# PS2_to_UART_revB.net
KiCad netlist of a schematic drawn in EAGLE
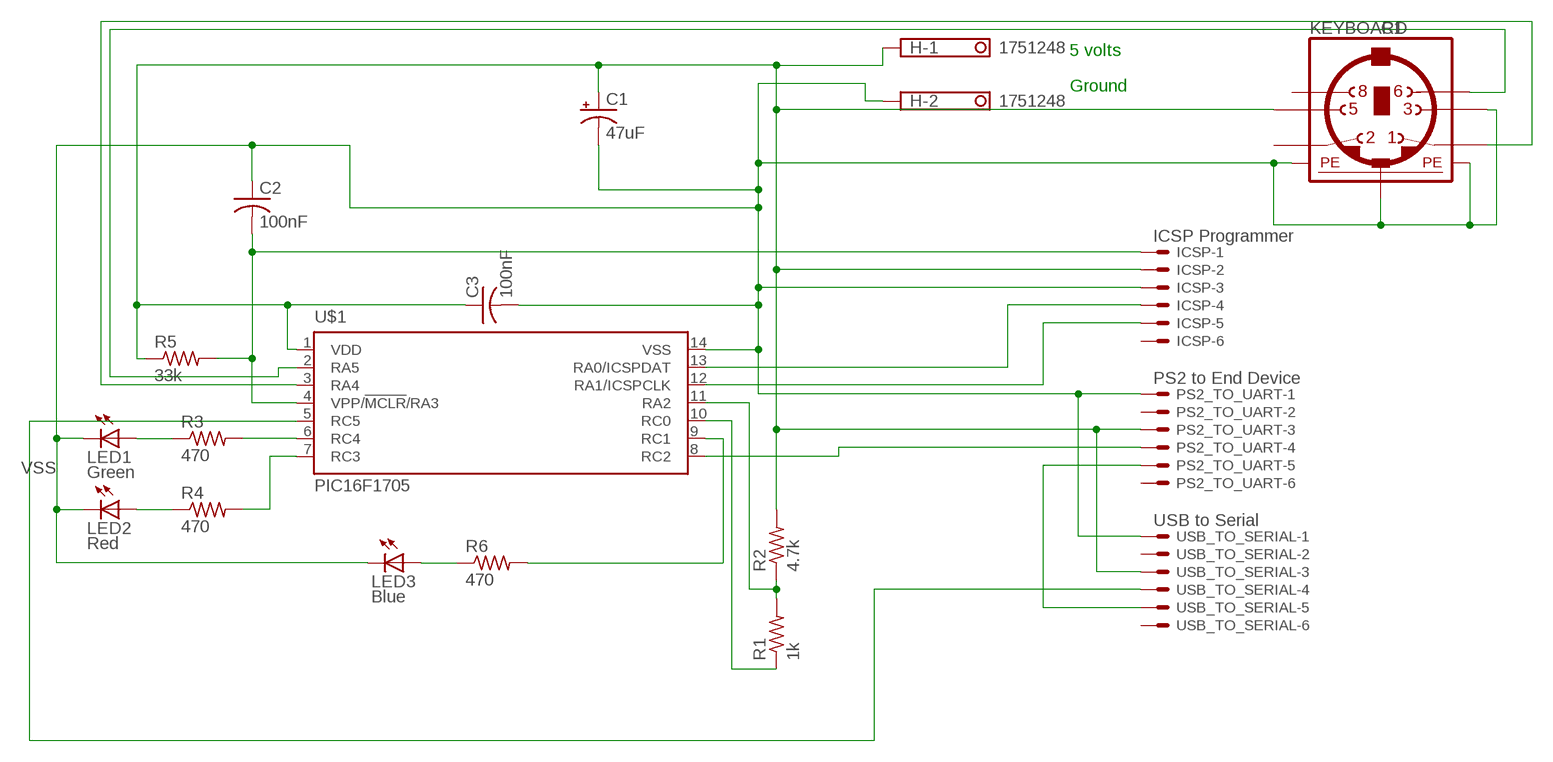
[diagram p0: schematic, sheet 1]

(export (version "E")
  (design (tool "Eeschema 10.0.6"))
  (components
    (comp (ref "C1")
      (value "47uF")
      (footprint "eagle-import:E2,5-7")
      (libsource (lib "eagle-import") (part "CPOL-USE2.5-7"))
    )
    (comp (ref "C2")
      (value "100nF")
      (footprint "eagle-import:C025-030X050")
      (libsource (lib "eagle-import") (part "C-US025-030X050"))
    )
    (comp (ref "C3")
      (value "100nF")
      (footprint "eagle-import:C025-030X050")
      (libsource (lib "eagle-import") (part "C-US025-030X050"))
    )
    (comp (ref "H")
      (value "1751248")
      (footprint "eagle-import:1751248")
      (libsource (lib "eagle-import") (part "1751248"))
    )
    (comp (ref "ICSP")
      (value "ICSP Programmer")
      (footprint "eagle-import:22-23-2061")
      (fields (field (name "MF") "MOLEX") (field (name "MPN") "22-23-2061"))
      (libsource (lib "eagle-import") (part "22-23-2061"))
    )
    (comp (ref "KEYBOARD")
      (value "C1")
      (footprint "eagle-import:M_DIN6")
      (libsource (lib "eagle-import") (part "MINI_DIN_6"))
    )
    (comp (ref "LED1")
      (value "Green")
      (footprint "eagle-import:LED5MM")
      (libsource (lib "eagle-import") (part "LED5MM"))
    )
    (comp (ref "LED2")
      (value "Red")
      (footprint "eagle-import:LED5MM")
      (libsource (lib "eagle-import") (part "LED5MM"))
    )
    (comp (ref "LED3")
      (value "Blue")
      (footprint "eagle-import:LED5MM")
      (libsource (lib "eagle-import") (part "LED5MM"))
    )
    (comp (ref "PS2_TO_UART")
      (value "PS2 to End Device")
      (footprint "eagle-import:22-23-2061")
      (fields (field (name "MF") "MOLEX") (field (name "MPN") "22-23-2061"))
      (libsource (lib "eagle-import") (part "22-23-2061"))
    )
    (comp (ref "R1")
      (value "1k")
      (footprint "eagle-import:0207_10")
      (libsource (lib "eagle-import") (part "R-US_0207/10"))
    )
    (comp (ref "R2")
      (value "4.7k")
      (footprint "eagle-import:0207_10")
      (libsource (lib "eagle-import") (part "R-US_0207/10"))
    )
    (comp (ref "R3")
      (value "470")
      (footprint "eagle-import:0207_10")
      (libsource (lib "eagle-import") (part "R-US_0207/10"))
    )
    (comp (ref "R4")
      (value "470")
      (footprint "eagle-import:0207_10")
      (libsource (lib "eagle-import") (part "R-US_0207/10"))
    )
    (comp (ref "R5")
      (value "33k")
      (footprint "eagle-import:0207_12")
      (libsource (lib "eagle-import") (part "resistor_R-US_0207/12"))
    )
    (comp (ref "R6")
      (value "470")
      (footprint "eagle-import:0207_10")
      (libsource (lib "eagle-import") (part "R-US_0207/10"))
    )
    (comp (ref "U$1")
      (value "PIC16F1705")
      (footprint "eagle-import:SO-14")
      (libsource (lib "eagle-import") (part "PIC16F1705"))
    )
    (comp (ref "USB_TO_SERIAL")
      (value "USB to Serial")
      (footprint "eagle-import:22-23-2061")
      (fields (field (name "MF") "MOLEX") (field (name "MPN") "22-23-2061"))
      (libsource (lib "eagle-import") (part "22-23-2061"))
    )
  )
  (nets
    (net (code "1") (name "/VSS") (class "Default")
      (node (ref "C1") (pin "-") (pinfunction "-_-") (pintype "passive"))
      (node (ref "C2") (pin "1") (pinfunction "1_1") (pintype "passive"))
      (node (ref "C3") (pin "2") (pinfunction "2_2") (pintype "passive"))
      (node (ref "H") (pin "2") (pinfunction "K_2") (pintype "passive"))
      (node (ref "ICSP") (pin "3") (pinfunction "S_3") (pintype "passive"))
      (node (ref "KEYBOARD") (pin "3") (pinfunction "3_3") (pintype "passive"))
      (node (ref "KEYBOARD") (pin "SH1") (pinfunction "PE1_SH1") (pintype "power_in"))
      (node (ref "KEYBOARD") (pin "SH2") (pinfunction "PE2_SH2") (pintype "power_in"))
      (node (ref "KEYBOARD") (pin "SH3") (pinfunction "PE3_SH3") (pintype "power_in"))
      (node (ref "LED1") (pin "K") (pinfunction "C_K") (pintype "passive"))
      (node (ref "LED2") (pin "K") (pinfunction "C_K") (pintype "passive"))
      (node (ref "LED3") (pin "K") (pinfunction "C_K") (pintype "passive"))
      (node (ref "PS2_TO_UART") (pin "1") (pinfunction "S_1") (pintype "passive"))
      (node (ref "U$1") (pin "14") (pinfunction "VSS_14") (pintype "bidirectional"))
      (node (ref "USB_TO_SERIAL") (pin "1") (pinfunction "S_1") (pintype "passive"))
    )
    (net (code "2") (name "Net-(HA-K)") (class "Default")
      (node (ref "C1") (pin "+") (pinfunction "+_+") (pintype "passive"))
      (node (ref "C3") (pin "1") (pinfunction "1_1") (pintype "passive"))
      (node (ref "H") (pin "1") (pinfunction "K_1") (pintype "passive"))
      (node (ref "ICSP") (pin "2") (pinfunction "S_2") (pintype "passive"))
      (node (ref "KEYBOARD") (pin "5") (pinfunction "5_5") (pintype "passive"))
      (node (ref "PS2_TO_UART") (pin "3") (pinfunction "S_3") (pintype "passive"))
      (node (ref "R2") (pin "2") (pinfunction "2_2") (pintype "passive"))
      (node (ref "R5") (pin "1") (pinfunction "1_1") (pintype "passive"))
      (node (ref "U$1") (pin "1") (pinfunction "VDD_1") (pintype "power_in"))
      (node (ref "USB_TO_SERIAL") (pin "3") (pinfunction "S_3") (pintype "passive"))
    )
    (net (code "3") (name "Net-(ICSPA-S)") (class "Default")
      (node (ref "C2") (pin "2") (pinfunction "2_2") (pintype "passive"))
      (node (ref "ICSP") (pin "1") (pinfunction "S_1") (pintype "passive"))
      (node (ref "R5") (pin "2") (pinfunction "2_2") (pintype "passive"))
      (node (ref "U$1") (pin "4") (pinfunction "VPP/~{MCLR}/RA3_4") (pintype "bidirectional"))
    )
    (net (code "4") (name "Net-(ICSPD-S)") (class "Default")
      (node (ref "ICSP") (pin "4") (pinfunction "S_4") (pintype "passive"))
      (node (ref "U$1") (pin "13") (pinfunction "RA0/ICSPDAT_13") (pintype "bidirectional"))
    )
    (net (code "5") (name "Net-(ICSPE-S)") (class "Default")
      (node (ref "ICSP") (pin "5") (pinfunction "S_5") (pintype "passive"))
      (node (ref "U$1") (pin "12") (pinfunction "RA1/ICSPCLK_12") (pintype "bidirectional"))
    )
    (net (code "6") (name "Net-(LED1-PadA)") (class "Default")
      (node (ref "LED1") (pin "A") (pinfunction "A_A") (pintype "passive"))
      (node (ref "R3") (pin "1") (pinfunction "1_1") (pintype "passive"))
    )
    (net (code "7") (name "Net-(LED2-PadA)") (class "Default")
      (node (ref "LED2") (pin "A") (pinfunction "A_A") (pintype "passive"))
      (node (ref "R4") (pin "1") (pinfunction "1_1") (pintype "passive"))
    )
    (net (code "8") (name "Net-(LED3-PadA)") (class "Default")
      (node (ref "LED3") (pin "A") (pinfunction "A_A") (pintype "passive"))
      (node (ref "R6") (pin "1") (pinfunction "1_1") (pintype "passive"))
    )
    (net (code "9") (name "Net-(PS2_TO_UARTD-S)") (class "Default")
      (node (ref "PS2_TO_UART") (pin "4") (pinfunction "S_4") (pintype "passive"))
      (node (ref "U$1") (pin "8") (pinfunction "RC2_8") (pintype "bidirectional"))
    )
    (net (code "10") (name "Net-(PS2_TO_UARTE-S)") (class "Default")
      (node (ref "PS2_TO_UART") (pin "5") (pinfunction "S_5") (pintype "passive"))
      (node (ref "USB_TO_SERIAL") (pin "5") (pinfunction "S_5") (pintype "passive"))
    )
    (net (code "11") (name "Net-(U$1-RA2)") (class "Default")
      (node (ref "R1") (pin "2") (pinfunction "2_2") (pintype "passive"))
      (node (ref "R2") (pin "1") (pinfunction "1_1") (pintype "passive"))
      (node (ref "U$1") (pin "11") (pinfunction "RA2_11") (pintype "bidirectional"))
    )
    (net (code "12") (name "Net-(U$1-RA4)") (class "Default")
      (node (ref "KEYBOARD") (pin "1") (pinfunction "1_1") (pintype "passive"))
      (node (ref "U$1") (pin "3") (pinfunction "RA4_3") (pintype "bidirectional"))
    )
    (net (code "13") (name "Net-(U$1-RA5)") (class "Default")
      (node (ref "KEYBOARD") (pin "6") (pinfunction "6_6") (pintype "passive"))
      (node (ref "U$1") (pin "2") (pinfunction "RA5_2") (pintype "bidirectional"))
    )
    (net (code "14") (name "Net-(U$1-RC0)") (class "Default")
      (node (ref "R1") (pin "1") (pinfunction "1_1") (pintype "passive"))
      (node (ref "U$1") (pin "10") (pinfunction "RC0_10") (pintype "bidirectional"))
    )
    (net (code "15") (name "Net-(U$1-RC1)") (class "Default")
      (node (ref "R6") (pin "2") (pinfunction "2_2") (pintype "passive"))
      (node (ref "U$1") (pin "9") (pinfunction "RC1_9") (pintype "bidirectional"))
    )
    (net (code "16") (name "Net-(U$1-RC3)") (class "Default")
      (node (ref "R4") (pin "2") (pinfunction "2_2") (pintype "passive"))
      (node (ref "U$1") (pin "7") (pinfunction "RC3_7") (pintype "bidirectional"))
    )
    (net (code "17") (name "Net-(U$1-RC4)") (class "Default")
      (node (ref "R3") (pin "2") (pinfunction "2_2") (pintype "passive"))
      (node (ref "U$1") (pin "6") (pinfunction "RC4_6") (pintype "bidirectional"))
    )
    (net (code "18") (name "Net-(U$1-RC5)") (class "Default")
      (node (ref "U$1") (pin "5") (pinfunction "RC5_5") (pintype "bidirectional"))
      (node (ref "USB_TO_SERIAL") (pin "4") (pinfunction "S_4") (pintype "passive"))
    )
    (net (code "19") (name "unconnected-(ICSPF-S-Pad6)") (class "Default")
      (node (ref "ICSP") (pin "6") (pinfunction "S_6") (pintype "passive"))
    )
    (net (code "20") (name "unconnected-(KEYBOARD-Pad2)") (class "Default")
      (node (ref "KEYBOARD") (pin "2") (pinfunction "2_2") (pintype "passive"))
    )
    (net (code "21") (name "unconnected-(KEYBOARD-Pad8)") (class "Default")
      (node (ref "KEYBOARD") (pin "8") (pinfunction "8_8") (pintype "passive"))
    )
    (net (code "22") (name "unconnected-(PS2_TO_UARTB-S-Pad2)") (class "Default")
      (node (ref "PS2_TO_UART") (pin "2") (pinfunction "S_2") (pintype "passive"))
    )
    (net (code "23") (name "unconnected-(PS2_TO_UARTF-S-Pad6)") (class "Default")
      (node (ref "PS2_TO_UART") (pin "6") (pinfunction "S_6") (pintype "passive"))
    )
    (net (code "24") (name "unconnected-(USB_TO_SERIALB-S-Pad2)") (class "Default")
      (node (ref "USB_TO_SERIAL") (pin "2") (pinfunction "S_2") (pintype "passive"))
    )
    (net (code "25") (name "unconnected-(USB_TO_SERIALF-S-Pad6)") (class "Default")
      (node (ref "USB_TO_SERIAL") (pin "6") (pinfunction "S_6") (pintype "passive"))
    )
  )
)
